# usb1wire.net
KiCad netlist of a schematic drawn in EAGLE
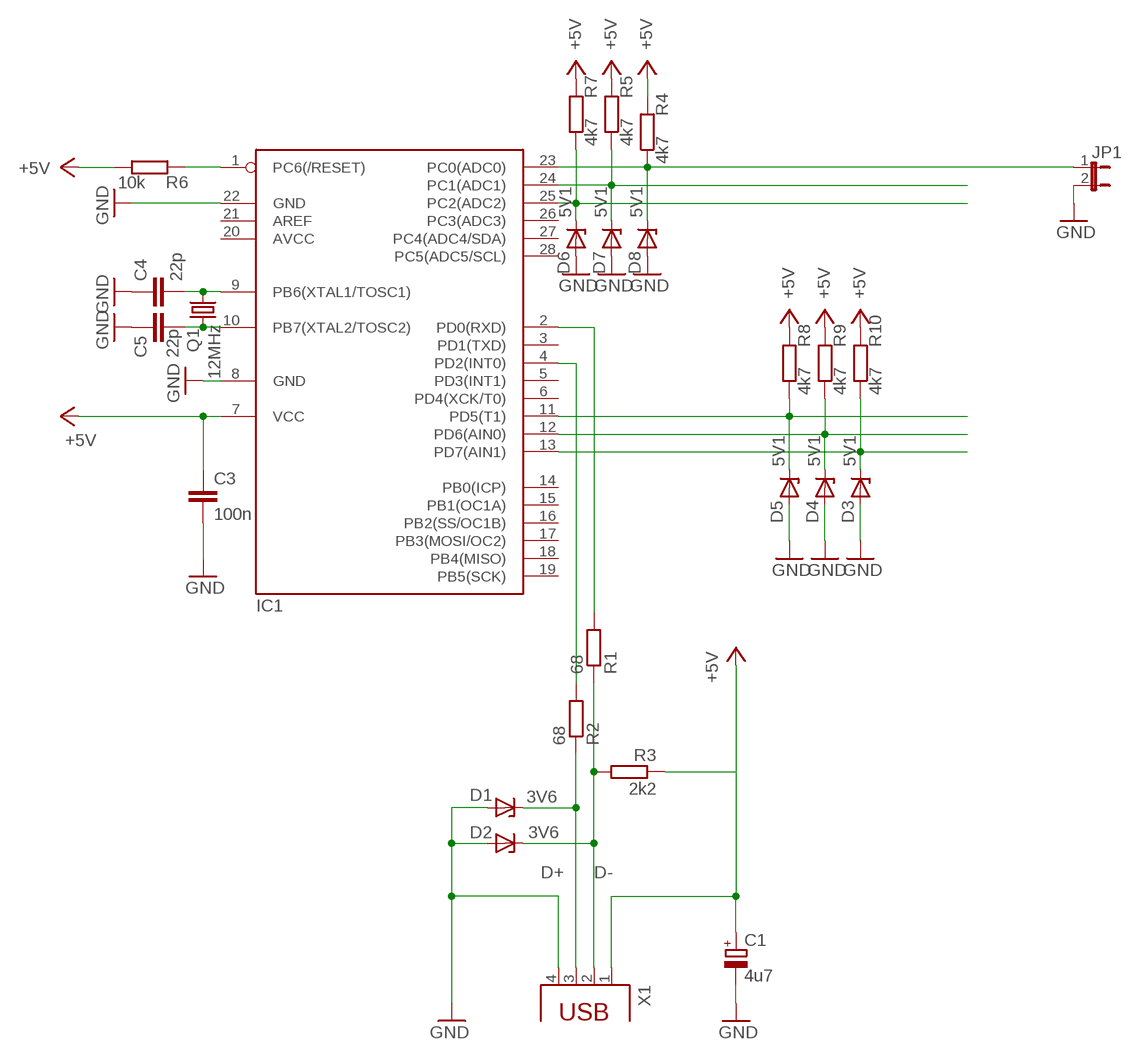
[diagram p0: schematic, sheet 1]

(export (version "E")
  (design (tool "Eeschema 10.0.6"))
  (components
    (comp (ref "C1")
      (value "4u7")
      (footprint "eagle-import:TT2D4")
      (libsource (lib "eagle-import") (part "CPOL-EUTT2D4"))
    )
    (comp (ref "C3")
      (value "100n")
      (footprint "eagle-import:C025-024X044")
      (libsource (lib "eagle-import") (part "C-EU025-024X044"))
    )
    (comp (ref "C4")
      (value "22p")
      (footprint "eagle-import:C025-024X044")
      (libsource (lib "eagle-import") (part "C-EU025-024X044"))
    )
    (comp (ref "C5")
      (value "22p")
      (footprint "eagle-import:C050-025X075")
      (libsource (lib "eagle-import") (part "C-EU050-025X075"))
    )
    (comp (ref "D1")
      (value "3V6")
      (footprint "eagle-import:DO34Z7")
      (libsource (lib "eagle-import") (part "ZENER-DIODEDO34-7"))
    )
    (comp (ref "D2")
      (value "3V6")
      (footprint "eagle-import:ZDIO-5")
      (libsource (lib "eagle-import") (part "ZENER-DIODEZD-5"))
    )
    (comp (ref "D3")
      (value "5V1")
      (footprint "eagle-import:ZDIO-5")
      (libsource (lib "eagle-import") (part "ZENER-DIODEZD-5"))
    )
    (comp (ref "D4")
      (value "5V1")
      (footprint "eagle-import:DO34Z7")
      (libsource (lib "eagle-import") (part "ZENER-DIODEDO34-7"))
    )
    (comp (ref "D5")
      (value "5V1")
      (footprint "eagle-import:DO41Z10")
      (libsource (lib "eagle-import") (part "ZENER-DIODEDO41Z10"))
    )
    (comp (ref "D6")
      (value "5V1")
      (footprint "eagle-import:SOD80C")
      (libsource (lib "eagle-import") (part "ZENER-DIODESOD80C"))
    )
    (comp (ref "D7")
      (value "5V1")
      (footprint "eagle-import:SOD80C")
      (libsource (lib "eagle-import") (part "ZENER-DIODESOD80C"))
    )
    (comp (ref "D8")
      (value "5V1")
      (footprint "eagle-import:SOD80C")
      (libsource (lib "eagle-import") (part "ZENER-DIODESOD80C"))
    )
    (comp (ref "IC1")
      (value "MEGA8-P")
      (footprint "eagle-import:DIL28-3")
      (libsource (lib "eagle-import") (part "MEGA8-P"))
    )
    (comp (ref "JP1")
      (value "JP1E")
      (footprint "eagle-import:JP1")
      (libsource (lib "eagle-import") (part "JP1E"))
    )
    (comp (ref "Q1")
      (value "12MHz")
      (footprint "eagle-import:TC26V")
      (libsource (lib "eagle-import") (part "CRYSTALTC26V"))
    )
    (comp (ref "R1")
      (value "68")
      (footprint "eagle-import:0207_10")
      (libsource (lib "eagle-import") (part "R-EU_0207/10"))
    )
    (comp (ref "R2")
      (value "68")
      (footprint "eagle-import:0204V")
      (libsource (lib "eagle-import") (part "R-EU_0204/2V"))
    )
    (comp (ref "R3")
      (value "2k2")
      (footprint "eagle-import:0207_2V")
      (libsource (lib "eagle-import") (part "R-EU_0207/2V"))
    )
    (comp (ref "R4")
      (value "4k7")
      (footprint "eagle-import:0207_15")
      (libsource (lib "eagle-import") (part "R-EU_0207/15"))
    )
    (comp (ref "R5")
      (value "4k7")
      (footprint "eagle-import:0207_12")
      (libsource (lib "eagle-import") (part "R-EU_0207/12"))
    )
    (comp (ref "R6")
      (value "10k")
      (footprint "eagle-import:0207_15")
      (libsource (lib "eagle-import") (part "R-EU_0207/15"))
    )
    (comp (ref "R7")
      (value "4k7")
      (footprint "eagle-import:0207_10")
      (libsource (lib "eagle-import") (part "R-EU_0207/10"))
    )
    (comp (ref "R8")
      (value "4k7")
      (footprint "eagle-import:0207_12")
      (libsource (lib "eagle-import") (part "R-EU_0207/12"))
    )
    (comp (ref "R9")
      (value "4k7")
      (footprint "eagle-import:0207_10")
      (libsource (lib "eagle-import") (part "R-EU_0207/10"))
    )
    (comp (ref "R10")
      (value "4k7")
      (footprint "eagle-import:0204_7")
      (libsource (lib "eagle-import") (part "R-EU_0204/7"))
    )
    (comp (ref "X1")
      (value "PN61729")
      (footprint "eagle-import:PN61729")
      (libsource (lib "eagle-import") (part "PN61729"))
    )
  )
  (nets
    (net (code "1") (name "+5V") (class "Default")
      (node (ref "C1") (pin "+") (pinfunction "+_+") (pintype "passive"))
      (node (ref "C3") (pin "1") (pinfunction "1_1") (pintype "passive"))
      (node (ref "IC1") (pin "7") (pinfunction "VCC_7") (pintype "power_in"))
      (node (ref "R10") (pin "2") (pinfunction "2_2") (pintype "passive"))
      (node (ref "R3") (pin "1") (pinfunction "1_1") (pintype "passive"))
      (node (ref "R4") (pin "2") (pinfunction "2_2") (pintype "passive"))
      (node (ref "R5") (pin "2") (pinfunction "2_2") (pintype "passive"))
      (node (ref "R6") (pin "1") (pinfunction "1_1") (pintype "passive"))
      (node (ref "R7") (pin "2") (pinfunction "2_2") (pintype "passive"))
      (node (ref "R8") (pin "2") (pinfunction "2_2") (pintype "passive"))
      (node (ref "R9") (pin "2") (pinfunction "2_2") (pintype "passive"))
      (node (ref "X1") (pin "1") (pinfunction "1_1") (pintype "passive"))
    )
    (net (code "2") (name "/AVCC") (class "Default")
      (node (ref "IC1") (pin "20") (pinfunction "AVCC_20") (pintype "power_in"))
    )
    (net (code "3") (name "/D+") (class "Default")
      (node (ref "D1") (pin "C") (pinfunction "C_C") (pintype "passive"))
      (node (ref "R2") (pin "1") (pinfunction "1_1") (pintype "passive"))
      (node (ref "X1") (pin "3") (pinfunction "3_3") (pintype "passive"))
    )
    (net (code "4") (name "/D-") (class "Default")
      (node (ref "D2") (pin "C") (pinfunction "C_C") (pintype "passive"))
      (node (ref "R1") (pin "1") (pinfunction "1_1") (pintype "passive"))
      (node (ref "R3") (pin "2") (pinfunction "2_2") (pintype "passive"))
      (node (ref "X1") (pin "2") (pinfunction "2_2") (pintype "passive"))
    )
    (net (code "5") (name "GND") (class "Default")
      (node (ref "C1") (pin "-") (pinfunction "-_-") (pintype "passive"))
      (node (ref "C3") (pin "2") (pinfunction "2_2") (pintype "passive"))
      (node (ref "C4") (pin "1") (pinfunction "1_1") (pintype "passive"))
      (node (ref "C5") (pin "1") (pinfunction "1_1") (pintype "passive"))
      (node (ref "D1") (pin "A") (pinfunction "A_A") (pintype "passive"))
      (node (ref "D2") (pin "A") (pinfunction "A_A") (pintype "passive"))
      (node (ref "D3") (pin "A") (pinfunction "A_A") (pintype "passive"))
      (node (ref "D4") (pin "A") (pinfunction "A_A") (pintype "passive"))
      (node (ref "D5") (pin "A") (pinfunction "A_A") (pintype "passive"))
      (node (ref "D6") (pin "A") (pinfunction "A_A") (pintype "passive"))
      (node (ref "D7") (pin "A") (pinfunction "A_A") (pintype "passive"))
      (node (ref "D8") (pin "A") (pinfunction "A_A") (pintype "passive"))
      (node (ref "IC1") (pin "22") (pinfunction "GND_22") (pintype "power_in"))
      (node (ref "IC1") (pin "8") (pinfunction "GND_8") (pintype "power_in"))
      (node (ref "JP1") (pin "2") (pinfunction "2_2") (pintype "passive"))
      (node (ref "X1") (pin "4") (pinfunction "4_4") (pintype "passive"))
    )
    (net (code "6") (name "Net-(IC1-PB6(XTAL1{slash}TOSC1))") (class "Default")
      (node (ref "C4") (pin "2") (pinfunction "2_2") (pintype "passive"))
      (node (ref "IC1") (pin "9") (pinfunction "PB6(XTAL1/TOSC1)_9") (pintype "bidirectional"))
      (node (ref "Q1") (pin "2") (pinfunction "2_2") (pintype "passive"))
    )
    (net (code "7") (name "Net-(IC1-PB7(XTAL2{slash}TOSC2))") (class "Default")
      (node (ref "C5") (pin "2") (pinfunction "2_2") (pintype "passive"))
      (node (ref "IC1") (pin "10") (pinfunction "PB7(XTAL2/TOSC2)_10") (pintype "bidirectional"))
      (node (ref "Q1") (pin "1") (pinfunction "1_1") (pintype "passive"))
    )
    (net (code "8") (name "Net-(IC1-PC0(ADC0))") (class "Default")
      (node (ref "D8") (pin "C") (pinfunction "C_C") (pintype "passive"))
      (node (ref "IC1") (pin "23") (pinfunction "PC0(ADC0)_23") (pintype "bidirectional"))
      (node (ref "JP1") (pin "1") (pinfunction "1_1") (pintype "passive"))
      (node (ref "R4") (pin "1") (pinfunction "1_1") (pintype "passive"))
    )
    (net (code "9") (name "Net-(IC1-PC1(ADC1))") (class "Default")
      (node (ref "D7") (pin "C") (pinfunction "C_C") (pintype "passive"))
      (node (ref "IC1") (pin "24") (pinfunction "PC1(ADC1)_24") (pintype "bidirectional"))
      (node (ref "R5") (pin "1") (pinfunction "1_1") (pintype "passive"))
    )
    (net (code "10") (name "Net-(IC1-PC2(ADC2))") (class "Default")
      (node (ref "D6") (pin "C") (pinfunction "C_C") (pintype "passive"))
      (node (ref "IC1") (pin "25") (pinfunction "PC2(ADC2)_25") (pintype "bidirectional"))
      (node (ref "R7") (pin "1") (pinfunction "1_1") (pintype "passive"))
    )
    (net (code "11") (name "Net-(IC1-PC6({slash}RESET))") (class "Default")
      (node (ref "IC1") (pin "1") (pinfunction "PC6(/RESET)_1") (pintype "bidirectional"))
      (node (ref "R6") (pin "2") (pinfunction "2_2") (pintype "passive"))
    )
    (net (code "12") (name "Net-(IC1-PD0(RXD))") (class "Default")
      (node (ref "IC1") (pin "2") (pinfunction "PD0(RXD)_2") (pintype "bidirectional"))
      (node (ref "R1") (pin "2") (pinfunction "2_2") (pintype "passive"))
    )
    (net (code "13") (name "Net-(IC1-PD2(INT0))") (class "Default")
      (node (ref "IC1") (pin "4") (pinfunction "PD2(INT0)_4") (pintype "bidirectional"))
      (node (ref "R2") (pin "2") (pinfunction "2_2") (pintype "passive"))
    )
    (net (code "14") (name "Net-(IC1-PD5(T1))") (class "Default")
      (node (ref "D5") (pin "C") (pinfunction "C_C") (pintype "passive"))
      (node (ref "IC1") (pin "11") (pinfunction "PD5(T1)_11") (pintype "bidirectional"))
      (node (ref "R8") (pin "1") (pinfunction "1_1") (pintype "passive"))
    )
    (net (code "15") (name "Net-(IC1-PD6(AIN0))") (class "Default")
      (node (ref "D4") (pin "C") (pinfunction "C_C") (pintype "passive"))
      (node (ref "IC1") (pin "12") (pinfunction "PD6(AIN0)_12") (pintype "bidirectional"))
      (node (ref "R9") (pin "1") (pinfunction "1_1") (pintype "passive"))
    )
    (net (code "16") (name "Net-(IC1-PD7(AIN1))") (class "Default")
      (node (ref "D3") (pin "C") (pinfunction "C_C") (pintype "passive"))
      (node (ref "IC1") (pin "13") (pinfunction "PD7(AIN1)_13") (pintype "bidirectional"))
      (node (ref "R10") (pin "1") (pinfunction "1_1") (pintype "passive"))
    )
    (net (code "17") (name "unconnected-(IC1-AREF-Pad21)") (class "Default")
      (node (ref "IC1") (pin "21") (pinfunction "AREF_21") (pintype "passive"))
    )
    (net (code "18") (name "unconnected-(IC1-PB0(ICP)-Pad14)") (class "Default")
      (node (ref "IC1") (pin "14") (pinfunction "PB0(ICP)_14") (pintype "bidirectional"))
    )
    (net (code "19") (name "unconnected-(IC1-PB1(OC1A)-Pad15)") (class "Default")
      (node (ref "IC1") (pin "15") (pinfunction "PB1(OC1A)_15") (pintype "bidirectional"))
    )
    (net (code "20") (name "unconnected-(IC1-PB2(SS{slash}OC1B)-Pad16)") (class "Default")
      (node (ref "IC1") (pin "16") (pinfunction "PB2(SS/OC1B)_16") (pintype "bidirectional"))
    )
    (net (code "21") (name "unconnected-(IC1-PB3(MOSI{slash}OC2)-Pad17)") (class "Default")
      (node (ref "IC1") (pin "17") (pinfunction "PB3(MOSI/OC2)_17") (pintype "bidirectional"))
    )
    (net (code "22") (name "unconnected-(IC1-PB4(MISO)-Pad18)") (class "Default")
      (node (ref "IC1") (pin "18") (pinfunction "PB4(MISO)_18") (pintype "bidirectional"))
    )
    (net (code "23") (name "unconnected-(IC1-PB5(SCK)-Pad19)") (class "Default")
      (node (ref "IC1") (pin "19") (pinfunction "PB5(SCK)_19") (pintype "bidirectional"))
    )
    (net (code "24") (name "unconnected-(IC1-PC3(ADC3)-Pad26)") (class "Default")
      (node (ref "IC1") (pin "26") (pinfunction "PC3(ADC3)_26") (pintype "bidirectional"))
    )
    (net (code "25") (name "unconnected-(IC1-PC4(ADC4{slash}SDA)-Pad27)") (class "Default")
      (node (ref "IC1") (pin "27") (pinfunction "PC4(ADC4/SDA)_27") (pintype "bidirectional"))
    )
    (net (code "26") (name "unconnected-(IC1-PC5(ADC5{slash}SCL)-Pad28)") (class "Default")
      (node (ref "IC1") (pin "28") (pinfunction "PC5(ADC5/SCL)_28") (pintype "bidirectional"))
    )
    (net (code "27") (name "unconnected-(IC1-PD1(TXD)-Pad3)") (class "Default")
      (node (ref "IC1") (pin "3") (pinfunction "PD1(TXD)_3") (pintype "bidirectional"))
    )
    (net (code "28") (name "unconnected-(IC1-PD3(INT1)-Pad5)") (class "Default")
      (node (ref "IC1") (pin "5") (pinfunction "PD3(INT1)_5") (pintype "bidirectional"))
    )
    (net (code "29") (name "unconnected-(IC1-PD4(XCK{slash}T0)-Pad6)") (class "Default")
      (node (ref "IC1") (pin "6") (pinfunction "PD4(XCK/T0)_6") (pintype "bidirectional"))
    )
  )
)
